# single_button.net
KiCad netlist of a schematic drawn in EAGLE
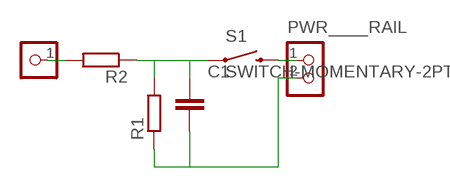
[diagram p0: schematic, sheet 1]

(export (version "E")
  (design (tool "Eeschema 10.0.6"))
  (components
    (comp (ref "C1")
      (value "CAPACITOR_NPOL-0805")
      (footprint "eagle-import:C805")
      (libsource (lib "eagle-import") (part "CAPACITOR_NPOL-0805"))
    )
    (comp (ref "PWR____RAIL")
      (value "CON_HEADER_1X02-PTH")
      (footprint "eagle-import:M1X2")
      (libsource (lib "eagle-import") (part "CON_HEADER_1X02-PTH"))
    )
    (comp (ref "R1")
      (value "RESISTORR805-0805")
      (footprint "eagle-import:R805")
      (libsource (lib "eagle-import") (part "RESISTOR-0805R805"))
    )
    (comp (ref "R2")
      (value "RESISTORR805-0805")
      (footprint "eagle-import:R805")
      (libsource (lib "eagle-import") (part "RESISTOR-0805R805"))
    )
    (comp (ref "S1")
      (value "SWITCH-MOMENTARY-2PTH")
      (footprint "eagle-import:TACTILE-PTH")
      (libsource (lib "eagle-import") (part "SWITCH-MOMENTARY-2PTH"))
    )
    (comp (ref "SIG")
      (value "CON_HEADER_1X01-PTH_08_17")
      (footprint "eagle-import:M1X2_08_17")
      (libsource (lib "eagle-import") (part "CON_HEADER_1X01-PTH_08_17"))
    )
  )
  (nets
    (net (code "1") (name "Net-(C1-Pad1)") (class "Default")
      (node (ref "C1") (pin "1") (pinfunction "1_1") (pintype "passive"))
      (node (ref "R1") (pin "2") (pinfunction "2_2") (pintype "passive"))
      (node (ref "R2") (pin "1") (pinfunction "1_1") (pintype "passive"))
      (node (ref "S1") (pin "1") (pinfunction "1_1") (pintype "passive"))
      (node (ref "S1") (pin "2") (pinfunction "1_2") (pintype "passive"))
    )
    (net (code "2") (name "Net-(C1-Pad2)") (class "Default")
      (node (ref "C1") (pin "2") (pinfunction "2_2") (pintype "passive"))
      (node (ref "PWR____RAIL") (pin "2") (pinfunction "2_2") (pintype "passive"))
      (node (ref "R1") (pin "1") (pinfunction "1_1") (pintype "passive"))
    )
    (net (code "3") (name "Net-(PWR____RAIL-Pad1)") (class "Default")
      (node (ref "PWR____RAIL") (pin "1") (pinfunction "1_1") (pintype "passive"))
      (node (ref "S1") (pin "3") (pinfunction "2_3") (pintype "passive"))
      (node (ref "S1") (pin "4") (pinfunction "2_4") (pintype "passive"))
    )
    (net (code "4") (name "Net-(R2-Pad2)") (class "Default")
      (node (ref "R2") (pin "2") (pinfunction "2_2") (pintype "passive"))
      (node (ref "SIG") (pin "1") (pinfunction "1_1") (pintype "passive"))
    )
  )
)
